# B293B_CoX_Amp.net
KiCad netlist of a schematic drawn in Altium Designer
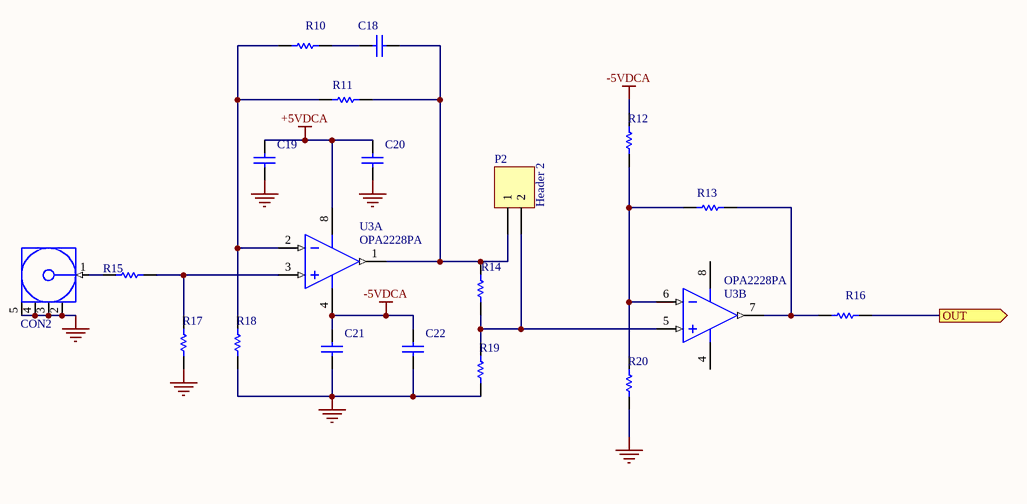
[diagram p0: B293B CoX Amp.SchDoc]

(export (version "E")
  (design (tool "Eeschema 10.0.6"))
  (components
    (comp (ref "C18")
      (value "CAP 47pF 50V 0805(2012)")
      (footprint "CAPC0805(2012)75_L")
      (description "CAP 47pF 50V ±5% 0805 (2012 Metric) Thickness 0.75mm SMD")
      (fields (field (name "TOLERANCE") "±5%"))
      (libsource (lib "Altium Content Vault") (part "CAP"))
    )
    (comp (ref "C19")
      (value "CAP 10uF 25V 0805(2012)")
      (footprint "CAPC0805(2012)145_N")
      (description "CAP 10uF 25V ±20% 0805 (2012 Metric) Thickness 1.45mm SMD")
      (fields (field (name "TOLERANCE") "±20%"))
      (libsource (lib "Altium Content Vault") (part "CAP"))
    )
    (comp (ref "C20")
      (value "CAP 10nF 25V 0805(2012)")
      (footprint "CAPC0805(2012)75_L")
      (description "CAP 10nF 25V ±10% 0805 (2012 Metric) Thickness 0.75mm SMD")
      (fields (field (name "TOLERANCE") "±10%"))
      (libsource (lib "Altium Content Vault") (part "CAP"))
    )
    (comp (ref "C21")
      (value "CAP 10nF 25V 0805(2012)")
      (footprint "CAPC0805(2012)75_L")
      (description "CAP 10nF 25V ±10% 0805 (2012 Metric) Thickness 0.75mm SMD")
      (fields (field (name "TOLERANCE") "±10%"))
      (libsource (lib "Altium Content Vault") (part "CAP"))
    )
    (comp (ref "C22")
      (value "CAP 10uF 25V 0805(2012)")
      (footprint "CAPC0805(2012)145_N")
      (description "CAP 10uF 25V ±20% 0805 (2012 Metric) Thickness 1.45mm SMD")
      (fields (field (name "TOLERANCE") "±20%"))
      (libsource (lib "Altium Content Vault") (part "CAP"))
    )
    (comp (ref "CON2")
      (value "SMA Vertical")
      (footprint "Matt PCB Library:SMA Vertical")
      (fields (field (name "MANUFACTURERS PART NO") "5-1814832-1"))
      (libsource (lib "Matt SCH Library") (part "SMA Vertical"))
    )
    (comp (ref "P2")
      (value "Header 2")
      (footprint "HDR1X2")
      (description "Header, 2-Pin")
      (fields (field (name "PUBLISHER") "Altium Limited"))
      (libsource (lib "Miscellaneous Connectors") (part "Header 2"))
    )
    (comp (ref "R10")
      (value "1K5 5% 0805(2012)")
      (footprint "RESC0805(2012)_L")
      (description "1K5 0.125W 5% 0805 (2012 Metric)  SMD")
      (fields (field (name "TOLERANCE") "5 %") (field (name "POWER") "0.125 W"))
      (libsource (lib "Altium Content Vault") (part "RES"))
    )
    (comp (ref "R11")
      (value "100K 5% 0805(2012)")
      (footprint "RESC0805(2012)_L")
      (description "100K 0.125W 5% 0805 (2012 Metric)  SMD")
      (fields (field (name "TOLERANCE") "5 %") (field (name "POWER") "0.125 W"))
      (libsource (lib "Altium Content Vault") (part "RES"))
    )
    (comp (ref "R12")
      (value "150K 5% 0805(2012)")
      (footprint "RESC0805(2012)_N")
      (description "150K 0.125W 5% 0805 (2012 Metric)  SMD")
      (fields (field (name "TOLERANCE") "5 %") (field (name "POWER") "0.125 W"))
      (libsource (lib "Altium Content Vault") (part "RES"))
    )
    (comp (ref "R13")
      (value "10K 5% 0805(2012)")
      (footprint "RESC0805(2012)_L")
      (description "10K 0.125W 5% 0805 (2012 Metric)  SMD")
      (fields (field (name "TOLERANCE") "5 %") (field (name "POWER") "0.125 W"))
      (libsource (lib "Altium Content Vault") (part "RES"))
    )
    (comp (ref "R14")
      (value "10K 5% 0805(2012)")
      (footprint "RESC0805(2012)_L")
      (description "10K 0.125W 5% 0805 (2012 Metric)  SMD")
      (fields (field (name "TOLERANCE") "5 %") (field (name "POWER") "0.125 W"))
      (libsource (lib "Altium Content Vault") (part "RES"))
    )
    (comp (ref "R15")
      (value "100R 5% 0805(2012)")
      (footprint "RESC0805(2012)_M")
      (description "100R 0.125W 5% 0805 (2012 Metric)  SMD")
      (fields (field (name "TOLERANCE") "5 %") (field (name "POWER") "0.125 W"))
      (libsource (lib "Altium Content Vault") (part "RES"))
    )
    (comp (ref "R16")
      (value "100R 5% 0805(2012)")
      (footprint "RESC0805(2012)_M")
      (description "100R 0.125W 5% 0805 (2012 Metric)  SMD")
      (fields (field (name "TOLERANCE") "5 %") (field (name "POWER") "0.125 W"))
      (libsource (lib "Altium Content Vault") (part "RES"))
    )
    (comp (ref "R17")
      (value "27K 5% 0805(2012)")
      (footprint "RESC0805(2012)_L")
      (description "27K 0.125W 5% 0805 (2012 Metric)  SMD")
      (fields (field (name "TOLERANCE") "5 %") (field (name "POWER") "0.125 W"))
      (libsource (lib "Altium Content Vault") (part "RES"))
    )
    (comp (ref "R18")
      (value "330R 5% 0805(2012)")
      (footprint "RESC0805(2012)_L")
      (description "330R 0.125W 5% 0805 (2012 Metric)  SMD")
      (fields (field (name "TOLERANCE") "5 %") (field (name "POWER") "0.125 W"))
      (libsource (lib "Altium Content Vault") (part "RES"))
    )
    (comp (ref "R19")
      (value "1K2 5% 0805(2012)")
      (footprint "RESC0805(2012)_N")
      (description "1K2 0.125W 5% 0805 (2012 Metric)  SMD")
      (fields (field (name "TOLERANCE") "5 %") (field (name "POWER") "0.125 W"))
      (libsource (lib "Altium Content Vault") (part "RES"))
    )
    (comp (ref "R20")
      (value "1K2 5% 0805(2012)")
      (footprint "RESC0805(2012)_N")
      (description "1K2 0.125W 5% 0805 (2012 Metric)  SMD")
      (fields (field (name "TOLERANCE") "5 %") (field (name "POWER") "0.125 W"))
      (libsource (lib "Altium Content Vault") (part "RES"))
    )
    (comp (ref "U3")
      (value "OPA2228PA")
      (footprint "TI-P8")
      (fields (field (name "MANUFACTURER") "Texas Instruments"))
      (libsource (lib "Altium Content Vault") (part "TI-OPA-8_2"))
    )
  )
  (nets
    (net (code "1") (name "+5VDCA") (class "Default")
      (node (ref "C19") (pin "2") (pinfunction "2_2") (pintype "passive"))
      (node (ref "C20") (pin "2") (pinfunction "2_2") (pintype "passive"))
      (node (ref "U3") (pin "8") (pinfunction "V+_8") (pintype "power_in"))
    )
    (net (code "2") (name "-5VDCA") (class "Default")
      (node (ref "C21") (pin "2") (pinfunction "2_2") (pintype "passive"))
      (node (ref "C22") (pin "2") (pinfunction "2_2") (pintype "passive"))
      (node (ref "R12") (pin "2") (pinfunction "2_2") (pintype "passive"))
      (node (ref "U3") (pin "4") (pinfunction "V-_4") (pintype "power_in"))
    )
    (net (code "3") (name "/OUT") (class "Default")
      (node (ref "R16") (pin "2") (pinfunction "2_2") (pintype "passive"))
    )
    (net (code "4") (name "GND") (class "Default")
      (node (ref "C19") (pin "1") (pinfunction "1_1") (pintype "passive"))
      (node (ref "C20") (pin "1") (pinfunction "1_1") (pintype "passive"))
      (node (ref "C21") (pin "1") (pinfunction "1_1") (pintype "passive"))
      (node (ref "C22") (pin "1") (pinfunction "1_1") (pintype "passive"))
      (node (ref "CON2") (pin "2") (pinfunction "GND_2") (pintype "power_in"))
      (node (ref "CON2") (pin "3") (pinfunction "GND_3") (pintype "power_in"))
      (node (ref "CON2") (pin "4") (pinfunction "GND_4") (pintype "power_in"))
      (node (ref "CON2") (pin "5") (pinfunction "GND_5") (pintype "power_in"))
      (node (ref "R17") (pin "1") (pinfunction "1_1") (pintype "passive"))
      (node (ref "R18") (pin "1") (pinfunction "1_1") (pintype "passive"))
      (node (ref "R19") (pin "1") (pinfunction "1_1") (pintype "passive"))
      (node (ref "R20") (pin "1") (pinfunction "1_1") (pintype "passive"))
    )
    (net (code "5") (name "Net-(C18-Pad2)") (class "Default")
      (node (ref "C18") (pin "2") (pinfunction "2_2") (pintype "passive"))
      (node (ref "R10") (pin "2") (pinfunction "2_2") (pintype "passive"))
    )
    (net (code "6") (name "Net-(CON2-Signal)") (class "Default")
      (node (ref "CON2") (pin "1") (pinfunction "Signal_1") (pintype "input"))
      (node (ref "R15") (pin "2") (pinfunction "2_2") (pintype "passive"))
    )
    (net (code "7") (name "Net-(U3A-IN_A+)") (class "Default")
      (node (ref "R15") (pin "1") (pinfunction "1_1") (pintype "passive"))
      (node (ref "R17") (pin "2") (pinfunction "2_2") (pintype "passive"))
      (node (ref "U3") (pin "3") (pinfunction "IN_A+_3") (pintype "input"))
    )
    (net (code "8") (name "Net-(U3A-IN_A-)") (class "Default")
      (node (ref "R10") (pin "1") (pinfunction "1_1") (pintype "passive"))
      (node (ref "R11") (pin "1") (pinfunction "1_1") (pintype "passive"))
      (node (ref "R18") (pin "2") (pinfunction "2_2") (pintype "passive"))
      (node (ref "U3") (pin "2") (pinfunction "IN_A-_2") (pintype "input"))
    )
    (net (code "9") (name "Net-(U3A-OUT_A)") (class "Default")
      (node (ref "C18") (pin "1") (pinfunction "1_1") (pintype "passive"))
      (node (ref "P2") (pin "1") (pinfunction "1_1") (pintype "passive"))
      (node (ref "R11") (pin "2") (pinfunction "2_2") (pintype "passive"))
      (node (ref "R14") (pin "2") (pinfunction "2_2") (pintype "passive"))
      (node (ref "U3") (pin "1") (pinfunction "OUT_A_1") (pintype "output"))
    )
    (net (code "10") (name "Net-(U3B-IN_B+)") (class "Default")
      (node (ref "P2") (pin "2") (pinfunction "2_2") (pintype "passive"))
      (node (ref "R14") (pin "1") (pinfunction "1_1") (pintype "passive"))
      (node (ref "R19") (pin "2") (pinfunction "2_2") (pintype "passive"))
      (node (ref "U3") (pin "5") (pinfunction "IN_B+_5") (pintype "input"))
    )
    (net (code "11") (name "Net-(U3B-IN_B-)") (class "Default")
      (node (ref "R12") (pin "1") (pinfunction "1_1") (pintype "passive"))
      (node (ref "R13") (pin "1") (pinfunction "1_1") (pintype "passive"))
      (node (ref "R20") (pin "2") (pinfunction "2_2") (pintype "passive"))
      (node (ref "U3") (pin "6") (pinfunction "IN_B-_6") (pintype "input"))
    )
    (net (code "12") (name "Net-(U3B-OUT_B)") (class "Default")
      (node (ref "R13") (pin "2") (pinfunction "2_2") (pintype "passive"))
      (node (ref "R16") (pin "1") (pinfunction "1_1") (pintype "passive"))
      (node (ref "U3") (pin "7") (pinfunction "OUT_B_7") (pintype "output"))
    )
    (net (code "13") (name "unconnected-(U3B-V+-Pad8)") (class "Default")
      (node (ref "U3") (pin "8") (pinfunction "V+_8") (pintype "power_in"))
    )
    (net (code "14") (name "unconnected-(U3B-V--Pad4)") (class "Default")
      (node (ref "U3") (pin "4") (pinfunction "V-_4") (pintype "power_in"))
    )
  )
)
